# myProject.net
KiCad netlist of a schematic drawn in EasyEDA Pro
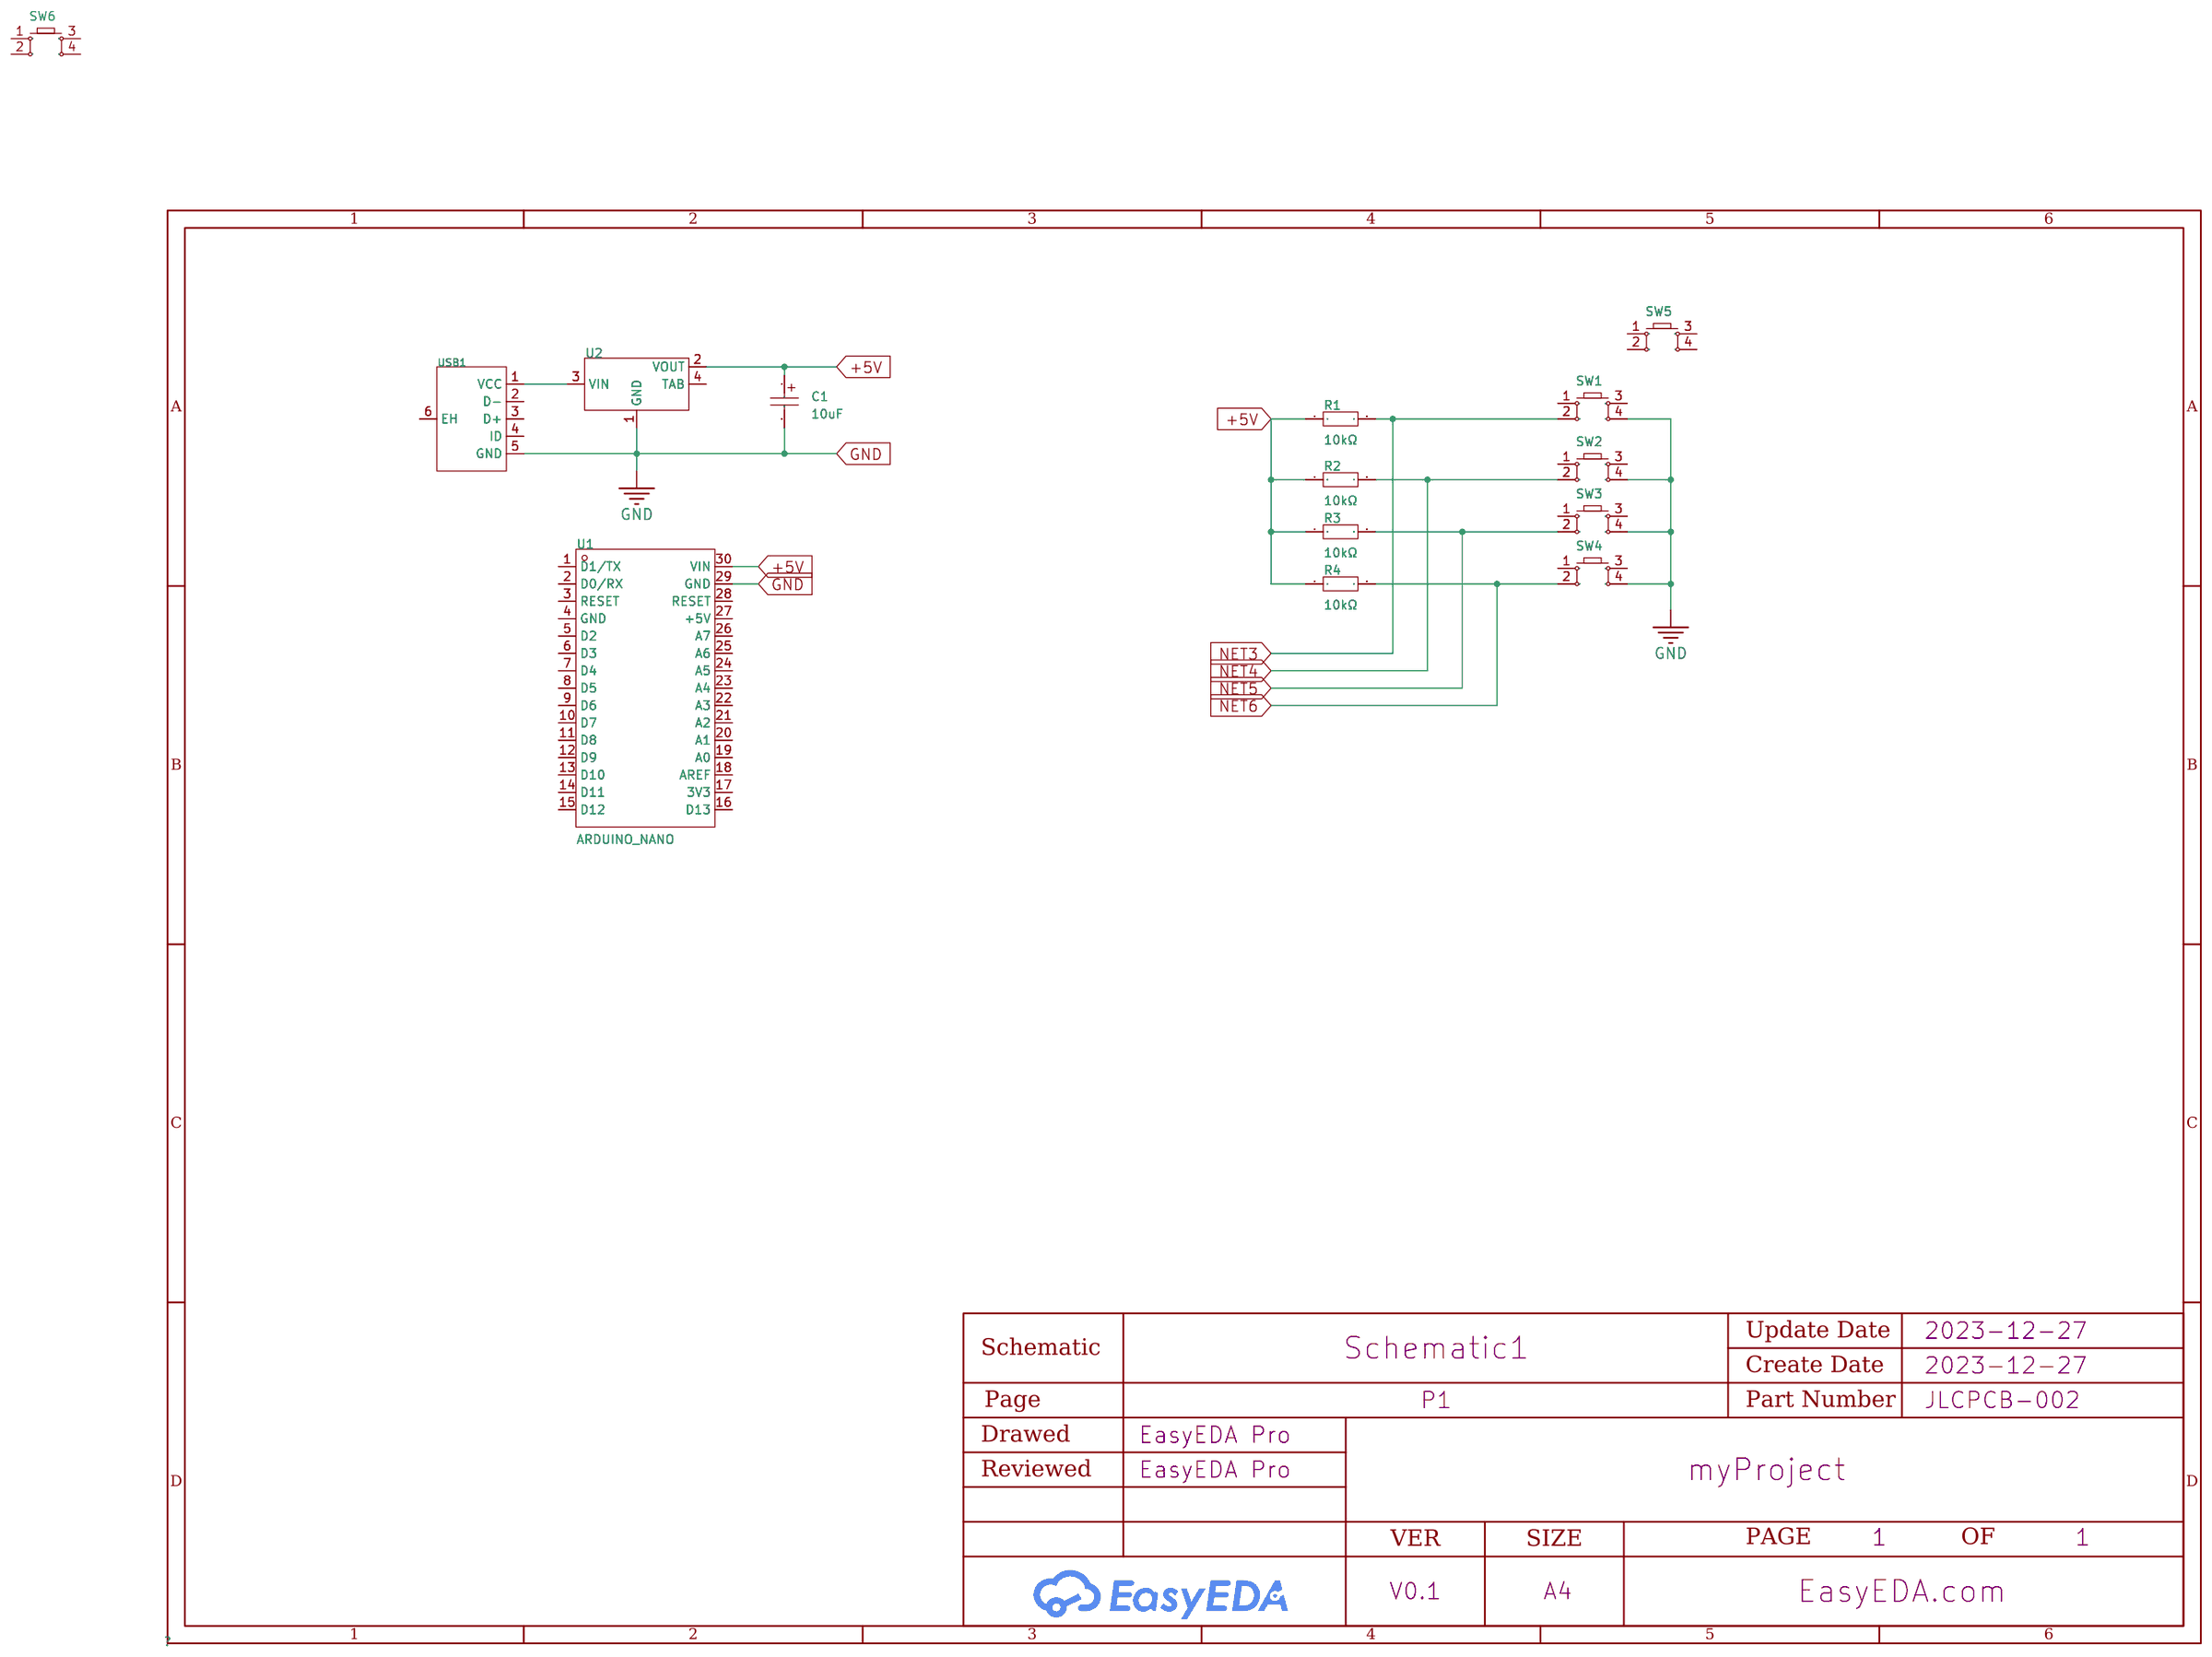
[diagram p0: schematic sheet]

(export (version "E")
  (design (tool "Eeschema 10.0.6"))
  (components
    (comp (ref "C1")
      (value "10uF")
      (footprint "easyedapro:CAP-SMD_BD3.0-L3.3-W3.3-RD")
      (libsource (lib "easyedapro") (part "C_Ele_SMD"))
    )
    (comp (ref "R1")
      (value "10kΩ")
      (footprint "easyedapro:R0201")
      (libsource (lib "easyedapro") (part "Res"))
    )
    (comp (ref "R2")
      (value "10kΩ")
      (footprint "easyedapro:R0201")
      (libsource (lib "easyedapro") (part "Res"))
    )
    (comp (ref "R3")
      (value "10kΩ")
      (footprint "easyedapro:R0201")
      (libsource (lib "easyedapro") (part "Res"))
    )
    (comp (ref "R4")
      (value "10kΩ")
      (footprint "easyedapro:R0201")
      (libsource (lib "easyedapro") (part "Res"))
    )
    (comp (ref "SW1")
      (value "~")
      (footprint "easyedapro:KEY-TH_4P-L6.0-W6.0-P3.90-LS6.5")
      (libsource (lib "easyedapro") (part "轻触按键"))
    )
    (comp (ref "SW2")
      (value "~")
      (footprint "easyedapro:KEY-TH_4P-L6.0-W6.0-P3.90-LS6.5")
      (libsource (lib "easyedapro") (part "轻触按键"))
    )
    (comp (ref "SW3")
      (value "~")
      (footprint "easyedapro:KEY-TH_4P-L6.0-W6.0-P3.90-LS6.5")
      (libsource (lib "easyedapro") (part "轻触按键"))
    )
    (comp (ref "SW4")
      (value "~")
      (footprint "easyedapro:KEY-TH_4P-L6.0-W6.0-P3.90-LS6.5")
      (libsource (lib "easyedapro") (part "轻触按键"))
    )
    (comp (ref "SW5")
      (value "~")
      (footprint "easyedapro:KEY-TH_4P-L6.0-W6.0-P3.90-LS6.5")
      (libsource (lib "easyedapro") (part "轻触按键"))
    )
    (comp (ref "SW6")
      (value "~")
      (footprint "easyedapro:KEY-TH_4P-L6.0-W6.0-P3.90-LS6.5")
      (libsource (lib "easyedapro") (part "轻触按键"))
    )
    (comp (ref "U1")
      (value "ARDUINO_NANO")
      (footprint "easyedapro:COMM-TH_ARDUINO_NANO")
      (libsource (lib "easyedapro") (part "ARDUINO_NANO"))
    )
    (comp (ref "U2")
      (value "~")
      (footprint "easyedapro:SOT-223_L6.7-W3.5-P2.30-BR")
      (libsource (lib "easyedapro") (part "AMS1117"))
    )
    (comp (ref "USB1")
      (value "~")
      (footprint "easyedapro:MINI-USB-SMD_MICRO-4P-DIP")
      (libsource (lib "easyedapro") (part "MICRO 4P DIP"))
    )
  )
  (nets
    (net (code "1") (name "+5V") (class "Default")
      (node (ref "C1") (pin "1") (pinfunction "1_1") (pintype "input"))
      (node (ref "R1") (pin "1") (pinfunction "1_1") (pintype "input"))
      (node (ref "R2") (pin "1") (pinfunction "1_1") (pintype "input"))
      (node (ref "R3") (pin "1") (pinfunction "1_1") (pintype "input"))
      (node (ref "R4") (pin "1") (pinfunction "1_1") (pintype "input"))
      (node (ref "U1") (pin "30") (pinfunction "VIN_30") (pintype "input"))
      (node (ref "U2") (pin "2") (pinfunction "VOUT_2") (pintype "input"))
    )
    (net (code "2") (name "GND") (class "Default")
      (node (ref "C1") (pin "2") (pinfunction "2_2") (pintype "input"))
      (node (ref "SW1") (pin "4") (pinfunction "4_4") (pintype "input"))
      (node (ref "SW2") (pin "4") (pinfunction "4_4") (pintype "input"))
      (node (ref "SW3") (pin "4") (pinfunction "4_4") (pintype "input"))
      (node (ref "SW4") (pin "4") (pinfunction "4_4") (pintype "input"))
      (node (ref "U1") (pin "29") (pinfunction "GND_29") (pintype "input"))
      (node (ref "U2") (pin "1") (pinfunction "GND_1") (pintype "input"))
      (node (ref "USB1") (pin "5") (pinfunction "GND_5") (pintype "input"))
    )
    (net (code "3") (name "NET3") (class "Default")
      (node (ref "R1") (pin "2") (pinfunction "2_2") (pintype "input"))
      (node (ref "SW1") (pin "2") (pinfunction "2_2") (pintype "input"))
    )
    (net (code "4") (name "NET4") (class "Default")
      (node (ref "R2") (pin "2") (pinfunction "2_2") (pintype "input"))
      (node (ref "SW2") (pin "2") (pinfunction "2_2") (pintype "input"))
    )
    (net (code "5") (name "NET5") (class "Default")
      (node (ref "R3") (pin "2") (pinfunction "2_2") (pintype "input"))
      (node (ref "SW3") (pin "2") (pinfunction "2_2") (pintype "input"))
    )
    (net (code "6") (name "NET6") (class "Default")
      (node (ref "R4") (pin "2") (pinfunction "2_2") (pintype "input"))
      (node (ref "SW4") (pin "2") (pinfunction "2_2") (pintype "input"))
    )
    (net (code "7") (name "Net-(U2-VIN)") (class "Default")
      (node (ref "U2") (pin "3") (pinfunction "VIN_3") (pintype "input"))
      (node (ref "USB1") (pin "1") (pinfunction "VCC_1") (pintype "input"))
    )
    (net (code "8") (name "unconnected-(SW1-Pad1)") (class "Default")
      (node (ref "SW1") (pin "1") (pinfunction "1_1") (pintype "input"))
    )
    (net (code "9") (name "unconnected-(SW1-Pad3)") (class "Default")
      (node (ref "SW1") (pin "3") (pinfunction "3_3") (pintype "input"))
    )
    (net (code "10") (name "unconnected-(SW2-Pad1)") (class "Default")
      (node (ref "SW2") (pin "1") (pinfunction "1_1") (pintype "input"))
    )
    (net (code "11") (name "unconnected-(SW2-Pad3)") (class "Default")
      (node (ref "SW2") (pin "3") (pinfunction "3_3") (pintype "input"))
    )
    (net (code "12") (name "unconnected-(SW3-Pad1)") (class "Default")
      (node (ref "SW3") (pin "1") (pinfunction "1_1") (pintype "input"))
    )
    (net (code "13") (name "unconnected-(SW3-Pad3)") (class "Default")
      (node (ref "SW3") (pin "3") (pinfunction "3_3") (pintype "input"))
    )
    (net (code "14") (name "unconnected-(SW4-Pad1)") (class "Default")
      (node (ref "SW4") (pin "1") (pinfunction "1_1") (pintype "input"))
    )
    (net (code "15") (name "unconnected-(SW4-Pad3)") (class "Default")
      (node (ref "SW4") (pin "3") (pinfunction "3_3") (pintype "input"))
    )
    (net (code "16") (name "unconnected-(SW5-Pad1)") (class "Default")
      (node (ref "SW5") (pin "1") (pinfunction "1_1") (pintype "input"))
    )
    (net (code "17") (name "unconnected-(SW5-Pad2)") (class "Default")
      (node (ref "SW5") (pin "2") (pinfunction "2_2") (pintype "input"))
    )
    (net (code "18") (name "unconnected-(SW5-Pad3)") (class "Default")
      (node (ref "SW5") (pin "3") (pinfunction "3_3") (pintype "input"))
    )
    (net (code "19") (name "unconnected-(SW5-Pad4)") (class "Default")
      (node (ref "SW5") (pin "4") (pinfunction "4_4") (pintype "input"))
    )
    (net (code "20") (name "unconnected-(SW6-Pad1)") (class "Default")
      (node (ref "SW6") (pin "1") (pinfunction "1_1") (pintype "input"))
    )
    (net (code "21") (name "unconnected-(SW6-Pad2)") (class "Default")
      (node (ref "SW6") (pin "2") (pinfunction "2_2") (pintype "input"))
    )
    (net (code "22") (name "unconnected-(SW6-Pad3)") (class "Default")
      (node (ref "SW6") (pin "3") (pinfunction "3_3") (pintype "input"))
    )
    (net (code "23") (name "unconnected-(SW6-Pad4)") (class "Default")
      (node (ref "SW6") (pin "4") (pinfunction "4_4") (pintype "input"))
    )
    (net (code "24") (name "unconnected-(U1-+5V-Pad27)") (class "Default")
      (node (ref "U1") (pin "27") (pinfunction "+5V_27") (pintype "input"))
    )
    (net (code "25") (name "unconnected-(U1-3V3-Pad17)") (class "Default")
      (node (ref "U1") (pin "17") (pinfunction "3V3_17") (pintype "input"))
    )
    (net (code "26") (name "unconnected-(U1-A0-Pad19)") (class "Default")
      (node (ref "U1") (pin "19") (pinfunction "A0_19") (pintype "input"))
    )
    (net (code "27") (name "unconnected-(U1-A1-Pad20)") (class "Default")
      (node (ref "U1") (pin "20") (pinfunction "A1_20") (pintype "input"))
    )
    (net (code "28") (name "unconnected-(U1-A2-Pad21)") (class "Default")
      (node (ref "U1") (pin "21") (pinfunction "A2_21") (pintype "input"))
    )
    (net (code "29") (name "unconnected-(U1-A3-Pad22)") (class "Default")
      (node (ref "U1") (pin "22") (pinfunction "A3_22") (pintype "input"))
    )
    (net (code "30") (name "unconnected-(U1-A4-Pad23)") (class "Default")
      (node (ref "U1") (pin "23") (pinfunction "A4_23") (pintype "input"))
    )
    (net (code "31") (name "unconnected-(U1-A5-Pad24)") (class "Default")
      (node (ref "U1") (pin "24") (pinfunction "A5_24") (pintype "input"))
    )
    (net (code "32") (name "unconnected-(U1-A6-Pad25)") (class "Default")
      (node (ref "U1") (pin "25") (pinfunction "A6_25") (pintype "input"))
    )
    (net (code "33") (name "unconnected-(U1-A7-Pad26)") (class "Default")
      (node (ref "U1") (pin "26") (pinfunction "A7_26") (pintype "input"))
    )
    (net (code "34") (name "unconnected-(U1-AREF-Pad18)") (class "Default")
      (node (ref "U1") (pin "18") (pinfunction "AREF_18") (pintype "input"))
    )
    (net (code "35") (name "unconnected-(U1-D0{slash}RX-Pad2)") (class "Default")
      (node (ref "U1") (pin "2") (pinfunction "D0/RX_2") (pintype "input"))
    )
    (net (code "36") (name "unconnected-(U1-D1{slash}TX-Pad1)") (class "Default")
      (node (ref "U1") (pin "1") (pinfunction "D1/TX_1") (pintype "input"))
    )
    (net (code "37") (name "unconnected-(U1-D2-Pad5)") (class "Default")
      (node (ref "U1") (pin "5") (pinfunction "D2_5") (pintype "input"))
    )
    (net (code "38") (name "unconnected-(U1-D3-Pad6)") (class "Default")
      (node (ref "U1") (pin "6") (pinfunction "D3_6") (pintype "input"))
    )
    (net (code "39") (name "unconnected-(U1-D4-Pad7)") (class "Default")
      (node (ref "U1") (pin "7") (pinfunction "D4_7") (pintype "input"))
    )
    (net (code "40") (name "unconnected-(U1-D5-Pad8)") (class "Default")
      (node (ref "U1") (pin "8") (pinfunction "D5_8") (pintype "input"))
    )
    (net (code "41") (name "unconnected-(U1-D6-Pad9)") (class "Default")
      (node (ref "U1") (pin "9") (pinfunction "D6_9") (pintype "input"))
    )
    (net (code "42") (name "unconnected-(U1-D7-Pad10)") (class "Default")
      (node (ref "U1") (pin "10") (pinfunction "D7_10") (pintype "input"))
    )
    (net (code "43") (name "unconnected-(U1-D8-Pad11)") (class "Default")
      (node (ref "U1") (pin "11") (pinfunction "D8_11") (pintype "input"))
    )
    (net (code "44") (name "unconnected-(U1-D9-Pad12)") (class "Default")
      (node (ref "U1") (pin "12") (pinfunction "D9_12") (pintype "input"))
    )
    (net (code "45") (name "unconnected-(U1-D10-Pad13)") (class "Default")
      (node (ref "U1") (pin "13") (pinfunction "D10_13") (pintype "input"))
    )
    (net (code "46") (name "unconnected-(U1-D11-Pad14)") (class "Default")
      (node (ref "U1") (pin "14") (pinfunction "D11_14") (pintype "input"))
    )
    (net (code "47") (name "unconnected-(U1-D12-Pad15)") (class "Default")
      (node (ref "U1") (pin "15") (pinfunction "D12_15") (pintype "input"))
    )
    (net (code "48") (name "unconnected-(U1-D13-Pad16)") (class "Default")
      (node (ref "U1") (pin "16") (pinfunction "D13_16") (pintype "input"))
    )
    (net (code "49") (name "unconnected-(U1-GND-Pad4)") (class "Default")
      (node (ref "U1") (pin "4") (pinfunction "GND_4") (pintype "input"))
    )
    (net (code "50") (name "unconnected-(U1-RESET-Pad3)") (class "Default")
      (node (ref "U1") (pin "3") (pinfunction "RESET_3") (pintype "input"))
    )
    (net (code "51") (name "unconnected-(U1-RESET-Pad28)") (class "Default")
      (node (ref "U1") (pin "28") (pinfunction "RESET_28") (pintype "input"))
    )
    (net (code "52") (name "unconnected-(U2-TAB-Pad4)") (class "Default")
      (node (ref "U2") (pin "4") (pinfunction "TAB_4") (pintype "input"))
    )
    (net (code "53") (name "unconnected-(USB1-D+-Pad3)") (class "Default")
      (node (ref "USB1") (pin "3") (pinfunction "D+_3") (pintype "input"))
    )
    (net (code "54") (name "unconnected-(USB1-D--Pad2)") (class "Default")
      (node (ref "USB1") (pin "2") (pinfunction "D-_2") (pintype "input"))
    )
    (net (code "55") (name "unconnected-(USB1-EH-Pad6)") (class "Default")
      (node (ref "USB1") (pin "6") (pinfunction "EH_6") (pintype "input"))
    )
    (net (code "56") (name "unconnected-(USB1-ID-Pad4)") (class "Default")
      (node (ref "USB1") (pin "4") (pinfunction "ID_4") (pintype "input"))
    )
  )
)
